# design.net
KiCad netlist of a schematic drawn in EasyEDA
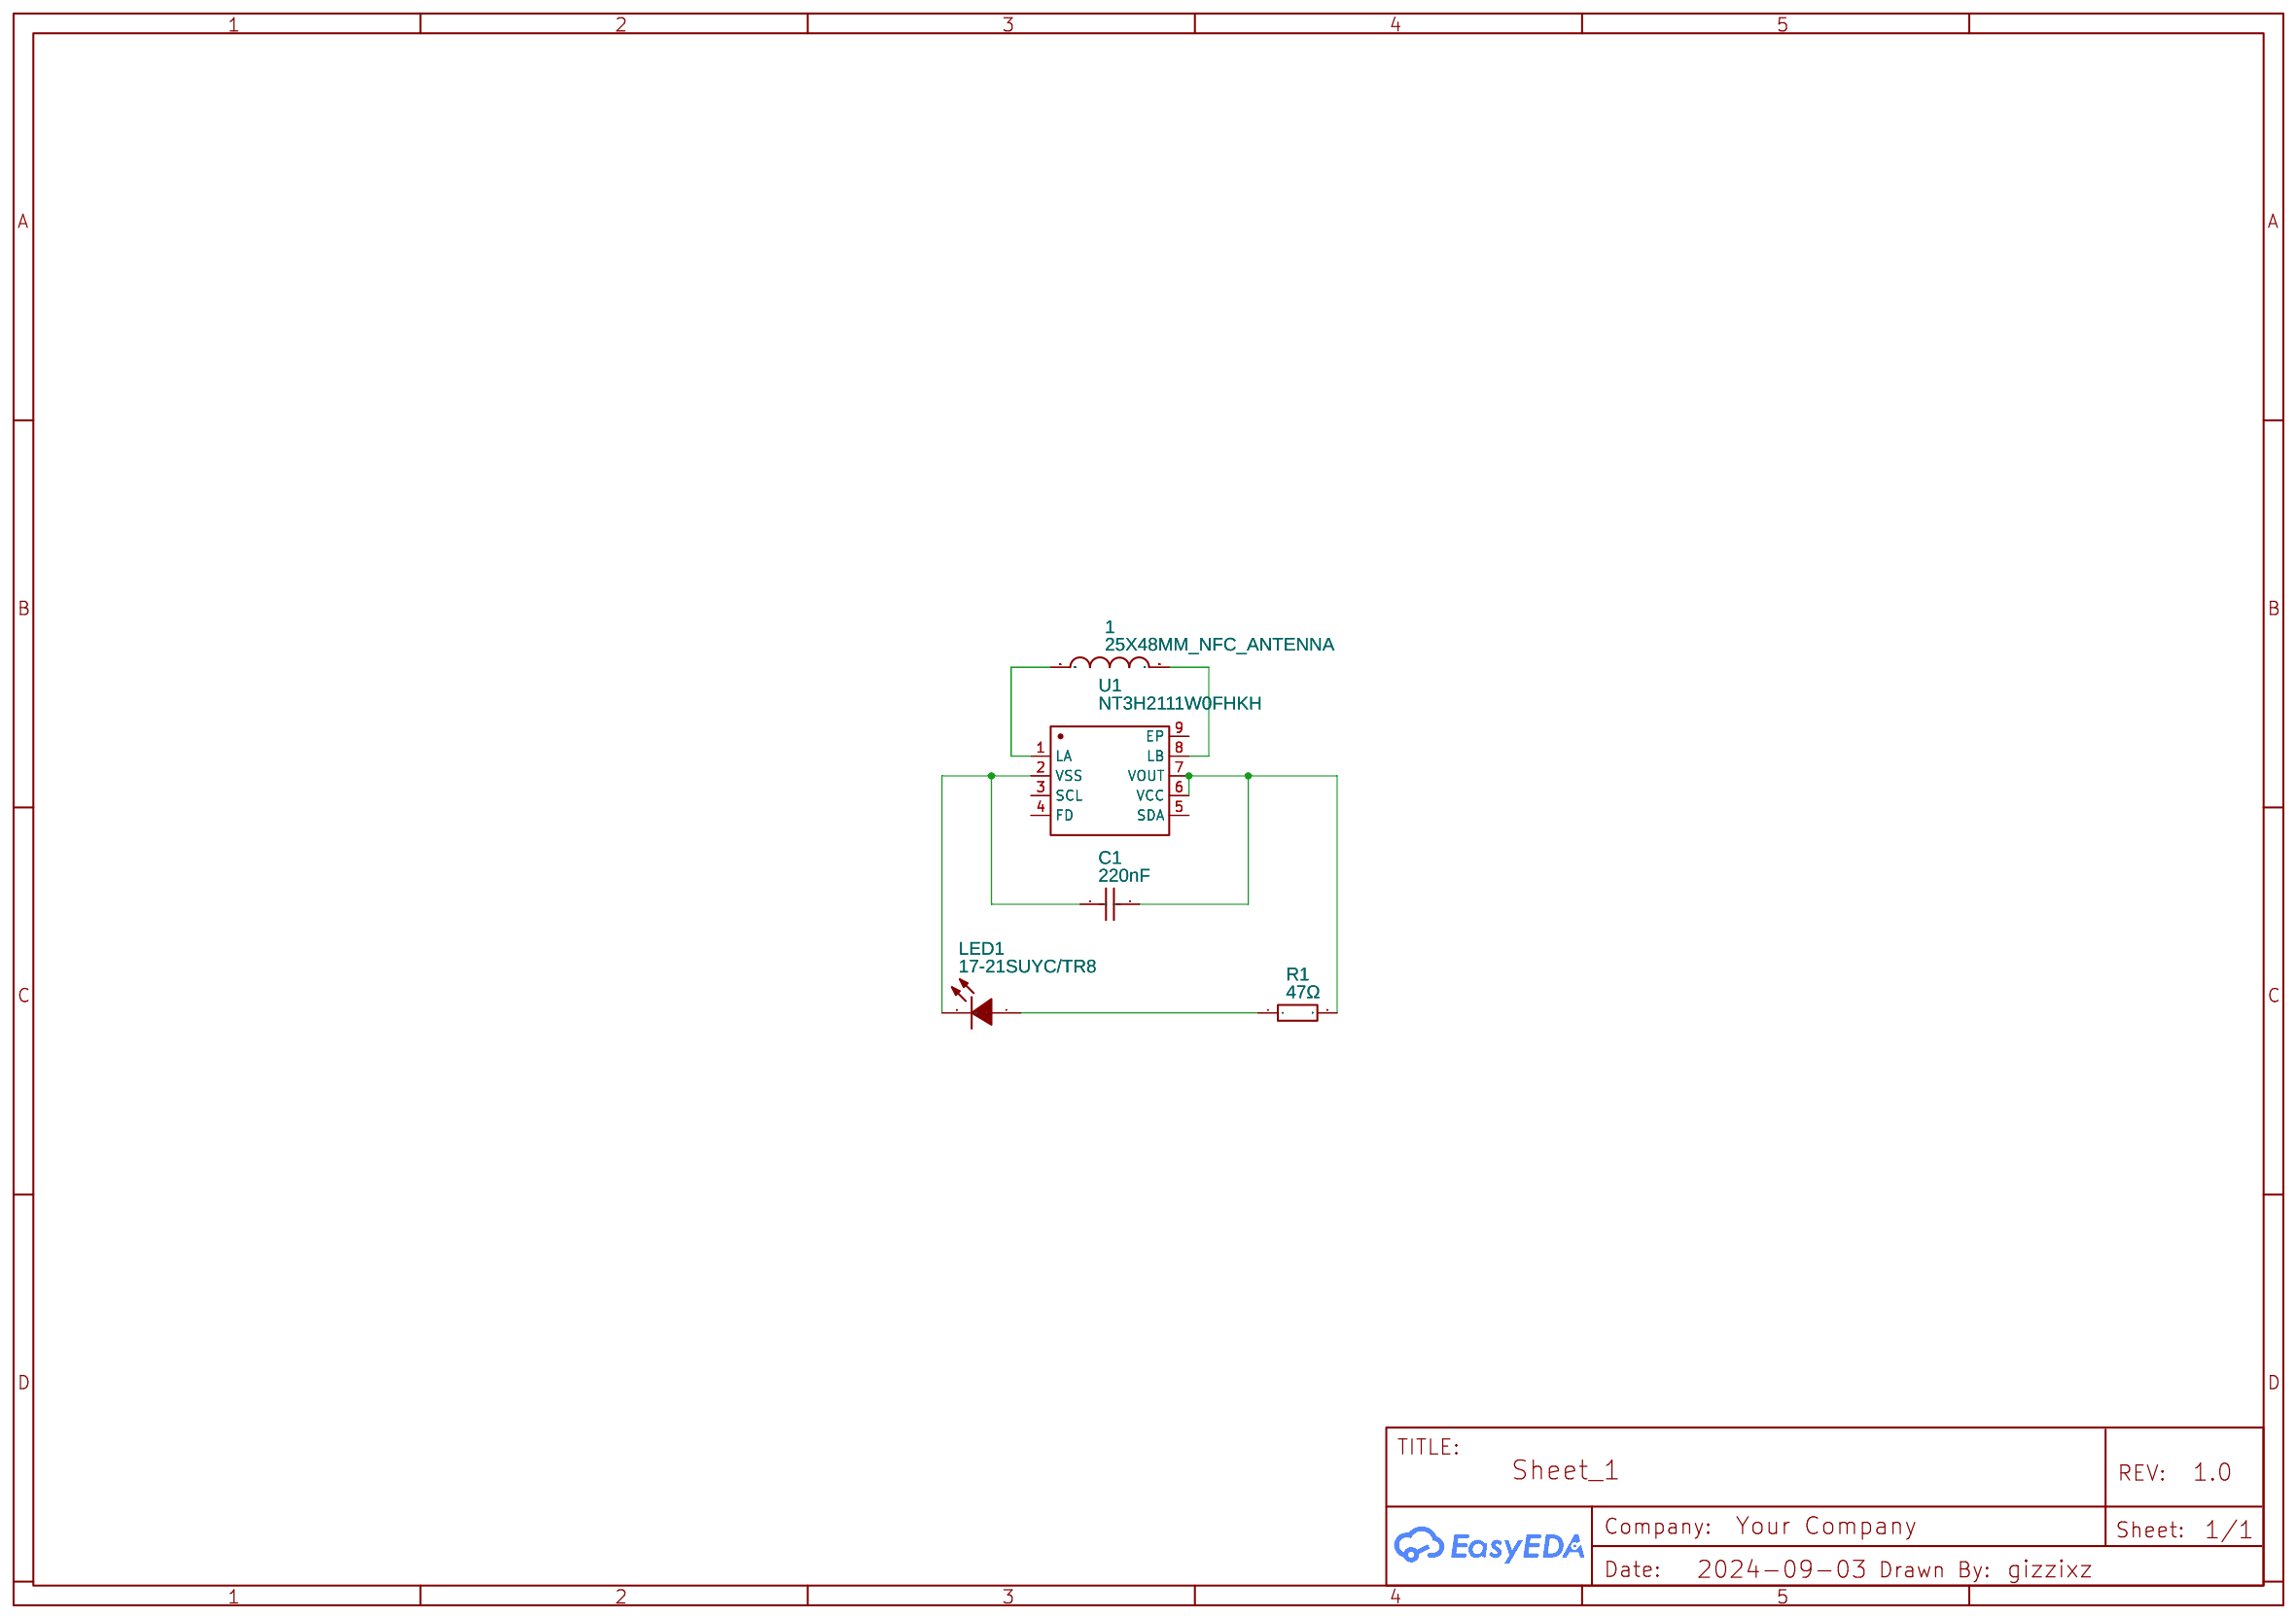
[diagram p0: schematic sheet]

(export (version "E")
  (design (tool "Eeschema 10.0.6"))
  (components
    (comp (ref "1") (value "25X48MM_NFC_ANTENNA") (libsource (lib "") (part "25X48MM_NFC_ANTENNA")))
    (comp (ref "C1")
      (value "220nF")
      (fields
        (field (name "Manufacturer Part") "CL10B224KA8NNNC")
        (field (name "Manufacturer") "SAMSUNG(三星)")
      )
      (libsource (lib "") (part "CL10B224KA8NNNC"))
    )
    (comp (ref "LED1")
      (value "17-21SUYC/TR8")
      (fields (field (name "Manufacturer Part") "KT-0805黄灯") (field (name "Manufacturer") "KENTO"))
      (libsource (lib "") (part "17-21SUYC/TR8"))
    )
    (comp (ref "R1")
      (value "47Ω")
      (fields
        (field (name "Manufacturer Part") "0603WAF470JT5E")
        (field (name "Manufacturer") "UNI-ROYAL(厚声)")
      )
      (libsource (lib "") (part "0603WAF470JT5E"))
    )
    (comp (ref "U1")
      (value "NT3H2111W0FHKH")
      (fields (field (name "Manufacturer") "NXP(恩智浦)"))
      (libsource (lib "") (part "NT3H2111W0FHKH"))
    )
  )
  (nets
    (net (code "1") (name "Net-(LED1-+)") (class "Default")
      (node (ref "LED1") (pin "1") (pinfunction "+_1") (pintype "unspecified"))
      (node (ref "R1") (pin "1") (pinfunction "1_1") (pintype "input"))
    )
    (net (code "2") (name "Net-(LED1--)") (class "Default")
      (node (ref "C1") (pin "1") (pinfunction "1_1") (pintype "input"))
      (node (ref "LED1") (pin "2") (pinfunction "-_2") (pintype "unspecified"))
      (node (ref "U1") (pin "2") (pinfunction "VSS_2") (pintype "unspecified"))
    )
    (net (code "3") (name "Net-(U1-LA)") (class "Default")
      (node (ref "1") (pin "P$1") (pinfunction "P$1_P$1") (pintype "bidirectional"))
      (node (ref "U1") (pin "1") (pinfunction "LA_1") (pintype "unspecified"))
    )
    (net (code "4") (name "Net-(U1-LB)") (class "Default")
      (node (ref "1") (pin "P$2") (pinfunction "P$2_P$2") (pintype "bidirectional"))
      (node (ref "U1") (pin "8") (pinfunction "LB_8") (pintype "unspecified"))
    )
    (net (code "5") (name "Net-(U1-VCC)") (class "Default")
      (node (ref "C1") (pin "2") (pinfunction "2_2") (pintype "input"))
      (node (ref "R1") (pin "2") (pinfunction "2_2") (pintype "input"))
      (node (ref "U1") (pin "6") (pinfunction "VCC_6") (pintype "unspecified"))
      (node (ref "U1") (pin "7") (pinfunction "VOUT_7") (pintype "unspecified"))
    )
    (net (code "6") (name "unconnected-(U1-EP-Pad9)") (class "Default")
      (node (ref "U1") (pin "9") (pinfunction "EP_9") (pintype "unspecified"))
    )
    (net (code "7") (name "unconnected-(U1-FD-Pad4)") (class "Default")
      (node (ref "U1") (pin "4") (pinfunction "FD_4") (pintype "unspecified"))
    )
    (net (code "8") (name "unconnected-(U1-SCL-Pad3)") (class "Default")
      (node (ref "U1") (pin "3") (pinfunction "SCL_3") (pintype "unspecified"))
    )
    (net (code "9") (name "unconnected-(U1-SDA-Pad5)") (class "Default")
      (node (ref "U1") (pin "5") (pinfunction "SDA_5") (pintype "unspecified"))
    )
  )
)
